# thermocouple.net
KiCad netlist of a schematic drawn in Altium Designer
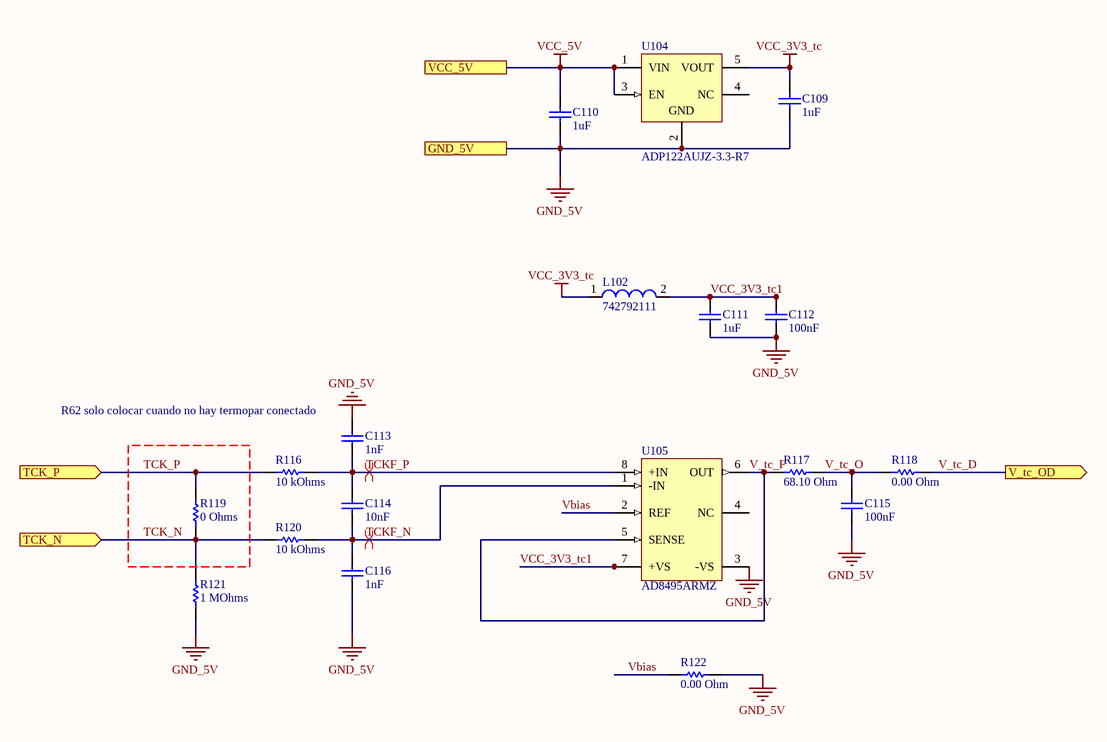
[diagram p0: thermocouple.SchDoc]

(export (version "E")
  (design (tool "Eeschema 10.0.6"))
  (components
    (comp (ref "C109")
      (value "1uF")
      (footprint "CAPC0603(1608)100_N")
      (description "CAP 1uF 50V ±20% 0603 (1608 Metric) Thickness 1mm SMD")
      (fields (field (name "TOLERANCE") "Â±20%") (field (name "Comment") "CAP 1uF 50V 0603(1608)"))
      (libsource (lib "Altium Content Vault") (part "CAP"))
    )
    (comp (ref "C110")
      (value "1uF")
      (footprint "CAPC0603(1608)100_N")
      (description "CAP 1uF 50V ±20% 0603 (1608 Metric) Thickness 1mm SMD")
      (fields (field (name "TOLERANCE") "Â±20%") (field (name "Comment") "CAP 1uF 50V 0603(1608)"))
      (libsource (lib "Altium Content Vault") (part "CAP"))
    )
    (comp (ref "C111")
      (value "1uF")
      (footprint "CAPC0603(1608)100_L")
      (description "CAP 1uF 50V ±20% 0603 (1608 Metric) Thickness 1mm SMD")
      (fields (field (name "TOLERANCE") "Â±20%") (field (name "Comment") "CAP 1uF 50V 0603(1608)"))
      (libsource (lib "Altium Content Vault") (part "CAP"))
    )
    (comp (ref "C112")
      (value "100nF")
      (footprint "CAPC0603(1608)100_L")
      (description "CAP 100nF 50V ±5% 0603 (1608 Metric) Thickness 1mm SMD")
      (fields (field (name "TOLERANCE") "Â±5%") (field (name "Comment") "CAP 100nF 50V 0603(1608)"))
      (libsource (lib "Altium Content Vault") (part "CAP"))
    )
    (comp (ref "C113")
      (value "1nF")
      (footprint "CAPC0603(1608)100_L")
      (description "CAP 1nF 25V ±5% 0603 (1608 Metric) Thickness 1mm SMD")
      (fields (field (name "TOLERANCE") "Â±5%") (field (name "Comment") "CAP 1nF 25V 0603(1608)"))
      (libsource (lib "Altium Content Vault") (part "CAP"))
    )
    (comp (ref "C114")
      (value "10nF")
      (footprint "CAPC0603(1608)100_L")
      (description "CAP 10nF 25V ±5% 0603 (1608 Metric) Thickness 1mm SMD")
      (fields (field (name "TOLERANCE") "Â±5%") (field (name "Comment") "CAP 10nF 25V 0603(1608)"))
      (libsource (lib "Altium Content Vault") (part "CAP"))
    )
    (comp (ref "C115")
      (value "100nF")
      (footprint "CAPC0603(1608)100_N")
      (description "CAP 100nF 10V ±10% 0603 (1608 Metric) Thickness 1mm SMD")
      (fields (field (name "TOLERANCE") "Â±10%") (field (name "Comment") "CAP 100nF 10V 0603(1608)"))
      (libsource (lib "Altium Content Vault") (part "CAP"))
    )
    (comp (ref "C116")
      (value "1nF")
      (footprint "CAPC0603(1608)100_L")
      (description "CAP 1nF 25V ±5% 0603 (1608 Metric) Thickness 1mm SMD")
      (fields (field (name "TOLERANCE") "Â±5%") (field (name "Comment") "CAP 1nF 25V 0603(1608)"))
      (libsource (lib "Altium Content Vault") (part "CAP"))
    )
    (comp (ref "L102")
      (value "742792111")
      (footprint "SMD-1206")
      (description "SMD EMI Suppression Ferrite Bead WE-CBF, Z = 26 Ohm")
      (libsource (lib "Altium Content Vault") (part "PAS-IND-INDUCTOR-2"))
    )
    (comp (ref "R116")
      (value "10 kOhms")
      (footprint "RESC3116X65X50NL20T20")
      (fields (field (name "PART NUMBER") "CRCW120610K0FKEAHP") (field (name "MANUFACTURER") "Vishay Dale"))
      (libsource (lib "Altium Content Vault") (part "RES"))
    )
    (comp (ref "R117")
      (value "68.10 Ohm")
      (footprint "RESC0805(2012)_N")
      (description "68R1 0.125W 1% 0805 (2012 Metric)  SMD")
      (fields (field (name "POWER") "0.125 W") (field (name "TOLERANCE") "1 %"))
      (libsource (lib "Altium Content Vault") (part "RES"))
    )
    (comp (ref "R118")
      (value "0.00 Ohm")
      (footprint "RESC0603(1608)_N")
      (description "Jumper 0603 (1608 Metric)")
      (fields (field (name "POWER") "None") (field (name "Comment") "Jumper 0603(1608)"))
      (libsource (lib "Altium Content Vault") (part "RES"))
    )
    (comp (ref "R119")
      (value "0 Ohms")
      (footprint "RESC3216X60X45LL10T20")
      (fields (field (name "PART NUMBER") "CRCW12060000Z0EB") (field (name "MANUFACTURER") "Vishay Dale"))
      (libsource (lib "Altium Content Vault") (part "RES"))
    )
    (comp (ref "R120")
      (value "10 kOhms")
      (footprint "RESC3116X65X50NL20T20")
      (fields (field (name "PART NUMBER") "CRCW120610K0FKEAHP") (field (name "MANUFACTURER") "Vishay Dale"))
      (libsource (lib "Altium Content Vault") (part "RES"))
    )
    (comp (ref "R121")
      (value "1 MOhms")
      (footprint "RESC3216X70X50LL05T20")
      (fields (field (name "MANUFACTURER") "Panasonic") (field (name "PART NUMBER") "ERJ-8GEYJ105V"))
      (libsource (lib "Altium Content Vault") (part "RES"))
    )
    (comp (ref "R122")
      (value "0.00 Ohm")
      (footprint "RESC0603(1608)_L")
      (description "Jumper 0603 (1608 Metric)")
      (fields (field (name "POWER") "None") (field (name "Comment") "Jumper 0603(1608)"))
      (libsource (lib "Altium Content Vault") (part "RES"))
    )
    (comp (ref "U104")
      (value "ADP122AUJZ-3.3-R7")
      (footprint "ADI-UJ-5_L")
      (fields (field (name "MANUFACTURER") "Analog Devices"))
      (libsource (lib "Altium Content Vault") (part "ADI-ADP1XX-UJ-5"))
    )
    (comp (ref "U105")
      (value "AD8495ARMZ")
      (footprint "DGK0008A_L")
      (fields (field (name "MANUFACTURER") "Analog Devices"))
      (libsource (lib "Altium_Library_POWERLAB") (part "AD8495ARMZ"))
    )
  )
  (nets
    (net (code "1") (name "/TCKF_N") (class "Default")
      (node (ref "C114") (pin "2") (pinfunction "2_2") (pintype "passive"))
      (node (ref "C116") (pin "1") (pinfunction "1_1") (pintype "passive"))
      (node (ref "R120") (pin "1") (pinfunction "1_1") (pintype "passive"))
      (node (ref "U105") (pin "1") (pinfunction "-IN_1") (pintype "input"))
    )
    (net (code "2") (name "/TCKF_P") (class "Default")
      (node (ref "C113") (pin "2") (pinfunction "2_2") (pintype "passive"))
      (node (ref "C114") (pin "1") (pinfunction "1_1") (pintype "passive"))
      (node (ref "R116") (pin "1") (pinfunction "1_1") (pintype "passive"))
      (node (ref "U105") (pin "8") (pinfunction "+IN_8") (pintype "input"))
    )
    (net (code "3") (name "/TCK_N") (class "Default")
      (node (ref "R119") (pin "1") (pinfunction "1_1") (pintype "passive"))
      (node (ref "R120") (pin "2") (pinfunction "2_2") (pintype "passive"))
      (node (ref "R121") (pin "2") (pinfunction "2_2") (pintype "passive"))
    )
    (net (code "4") (name "/TCK_P") (class "Default")
      (node (ref "R116") (pin "2") (pinfunction "2_2") (pintype "passive"))
      (node (ref "R119") (pin "2") (pinfunction "2_2") (pintype "passive"))
    )
    (net (code "5") (name "/VCC_3V3_tc1") (class "Default")
      (node (ref "C111") (pin "2") (pinfunction "2_2") (pintype "passive"))
      (node (ref "C112") (pin "2") (pinfunction "2_2") (pintype "passive"))
      (node (ref "L102") (pin "2") (pinfunction "2_2") (pintype "passive"))
      (node (ref "U105") (pin "7") (pinfunction "+VS_7") (pintype "power_in"))
    )
    (net (code "6") (name "/V_tc_D") (class "Default")
      (node (ref "R118") (pin "1") (pinfunction "1_1") (pintype "passive"))
    )
    (net (code "7") (name "/V_tc_F") (class "Default")
      (node (ref "R117") (pin "2") (pinfunction "2_2") (pintype "passive"))
      (node (ref "U105") (pin "5") (pinfunction "SENSE_5") (pintype "input"))
      (node (ref "U105") (pin "6") (pinfunction "OUT_6") (pintype "output"))
    )
    (net (code "8") (name "/V_tc_O") (class "Default")
      (node (ref "C115") (pin "2") (pinfunction "2_2") (pintype "passive"))
      (node (ref "R117") (pin "1") (pinfunction "1_1") (pintype "passive"))
      (node (ref "R118") (pin "2") (pinfunction "2_2") (pintype "passive"))
    )
    (net (code "9") (name "/Vbias") (class "Default")
      (node (ref "R122") (pin "1") (pinfunction "1_1") (pintype "passive"))
      (node (ref "U105") (pin "2") (pinfunction "REF_2") (pintype "input"))
    )
    (net (code "10") (name "GND_5V") (class "Default")
      (node (ref "C109") (pin "1") (pinfunction "1_1") (pintype "passive"))
      (node (ref "C110") (pin "1") (pinfunction "1_1") (pintype "passive"))
      (node (ref "C111") (pin "1") (pinfunction "1_1") (pintype "passive"))
      (node (ref "C112") (pin "1") (pinfunction "1_1") (pintype "passive"))
      (node (ref "C113") (pin "1") (pinfunction "1_1") (pintype "passive"))
      (node (ref "C115") (pin "1") (pinfunction "1_1") (pintype "passive"))
      (node (ref "C116") (pin "2") (pinfunction "2_2") (pintype "passive"))
      (node (ref "R121") (pin "1") (pinfunction "1_1") (pintype "passive"))
      (node (ref "R122") (pin "2") (pinfunction "2_2") (pintype "passive"))
      (node (ref "U104") (pin "2") (pinfunction "GND_2") (pintype "power_in"))
      (node (ref "U105") (pin "3") (pinfunction "-VS_3") (pintype "power_in"))
    )
    (net (code "11") (name "VCC_3V3_tc") (class "Default")
      (node (ref "C109") (pin "2") (pinfunction "2_2") (pintype "passive"))
      (node (ref "L102") (pin "1") (pinfunction "1_1") (pintype "passive"))
      (node (ref "U104") (pin "5") (pinfunction "VOUT_5") (pintype "power_in"))
    )
    (net (code "12") (name "VCC_5V") (class "Default")
      (node (ref "C110") (pin "2") (pinfunction "2_2") (pintype "passive"))
      (node (ref "U104") (pin "1") (pinfunction "VIN_1") (pintype "power_in"))
      (node (ref "U104") (pin "3") (pinfunction "EN_3") (pintype "input"))
    )
    (net (code "13") (name "unconnected-(U104-NC-Pad4)") (class "Default")
      (node (ref "U104") (pin "4") (pinfunction "NC_4") (pintype "passive"))
    )
    (net (code "14") (name "unconnected-(U105-NC-Pad4)") (class "Default")
      (node (ref "U105") (pin "4") (pinfunction "NC_4") (pintype "passive"))
    )
  )
)
